# SiLPA_HE_LVDS_IFC.net
KiCad netlist of a schematic drawn in Altium Designer
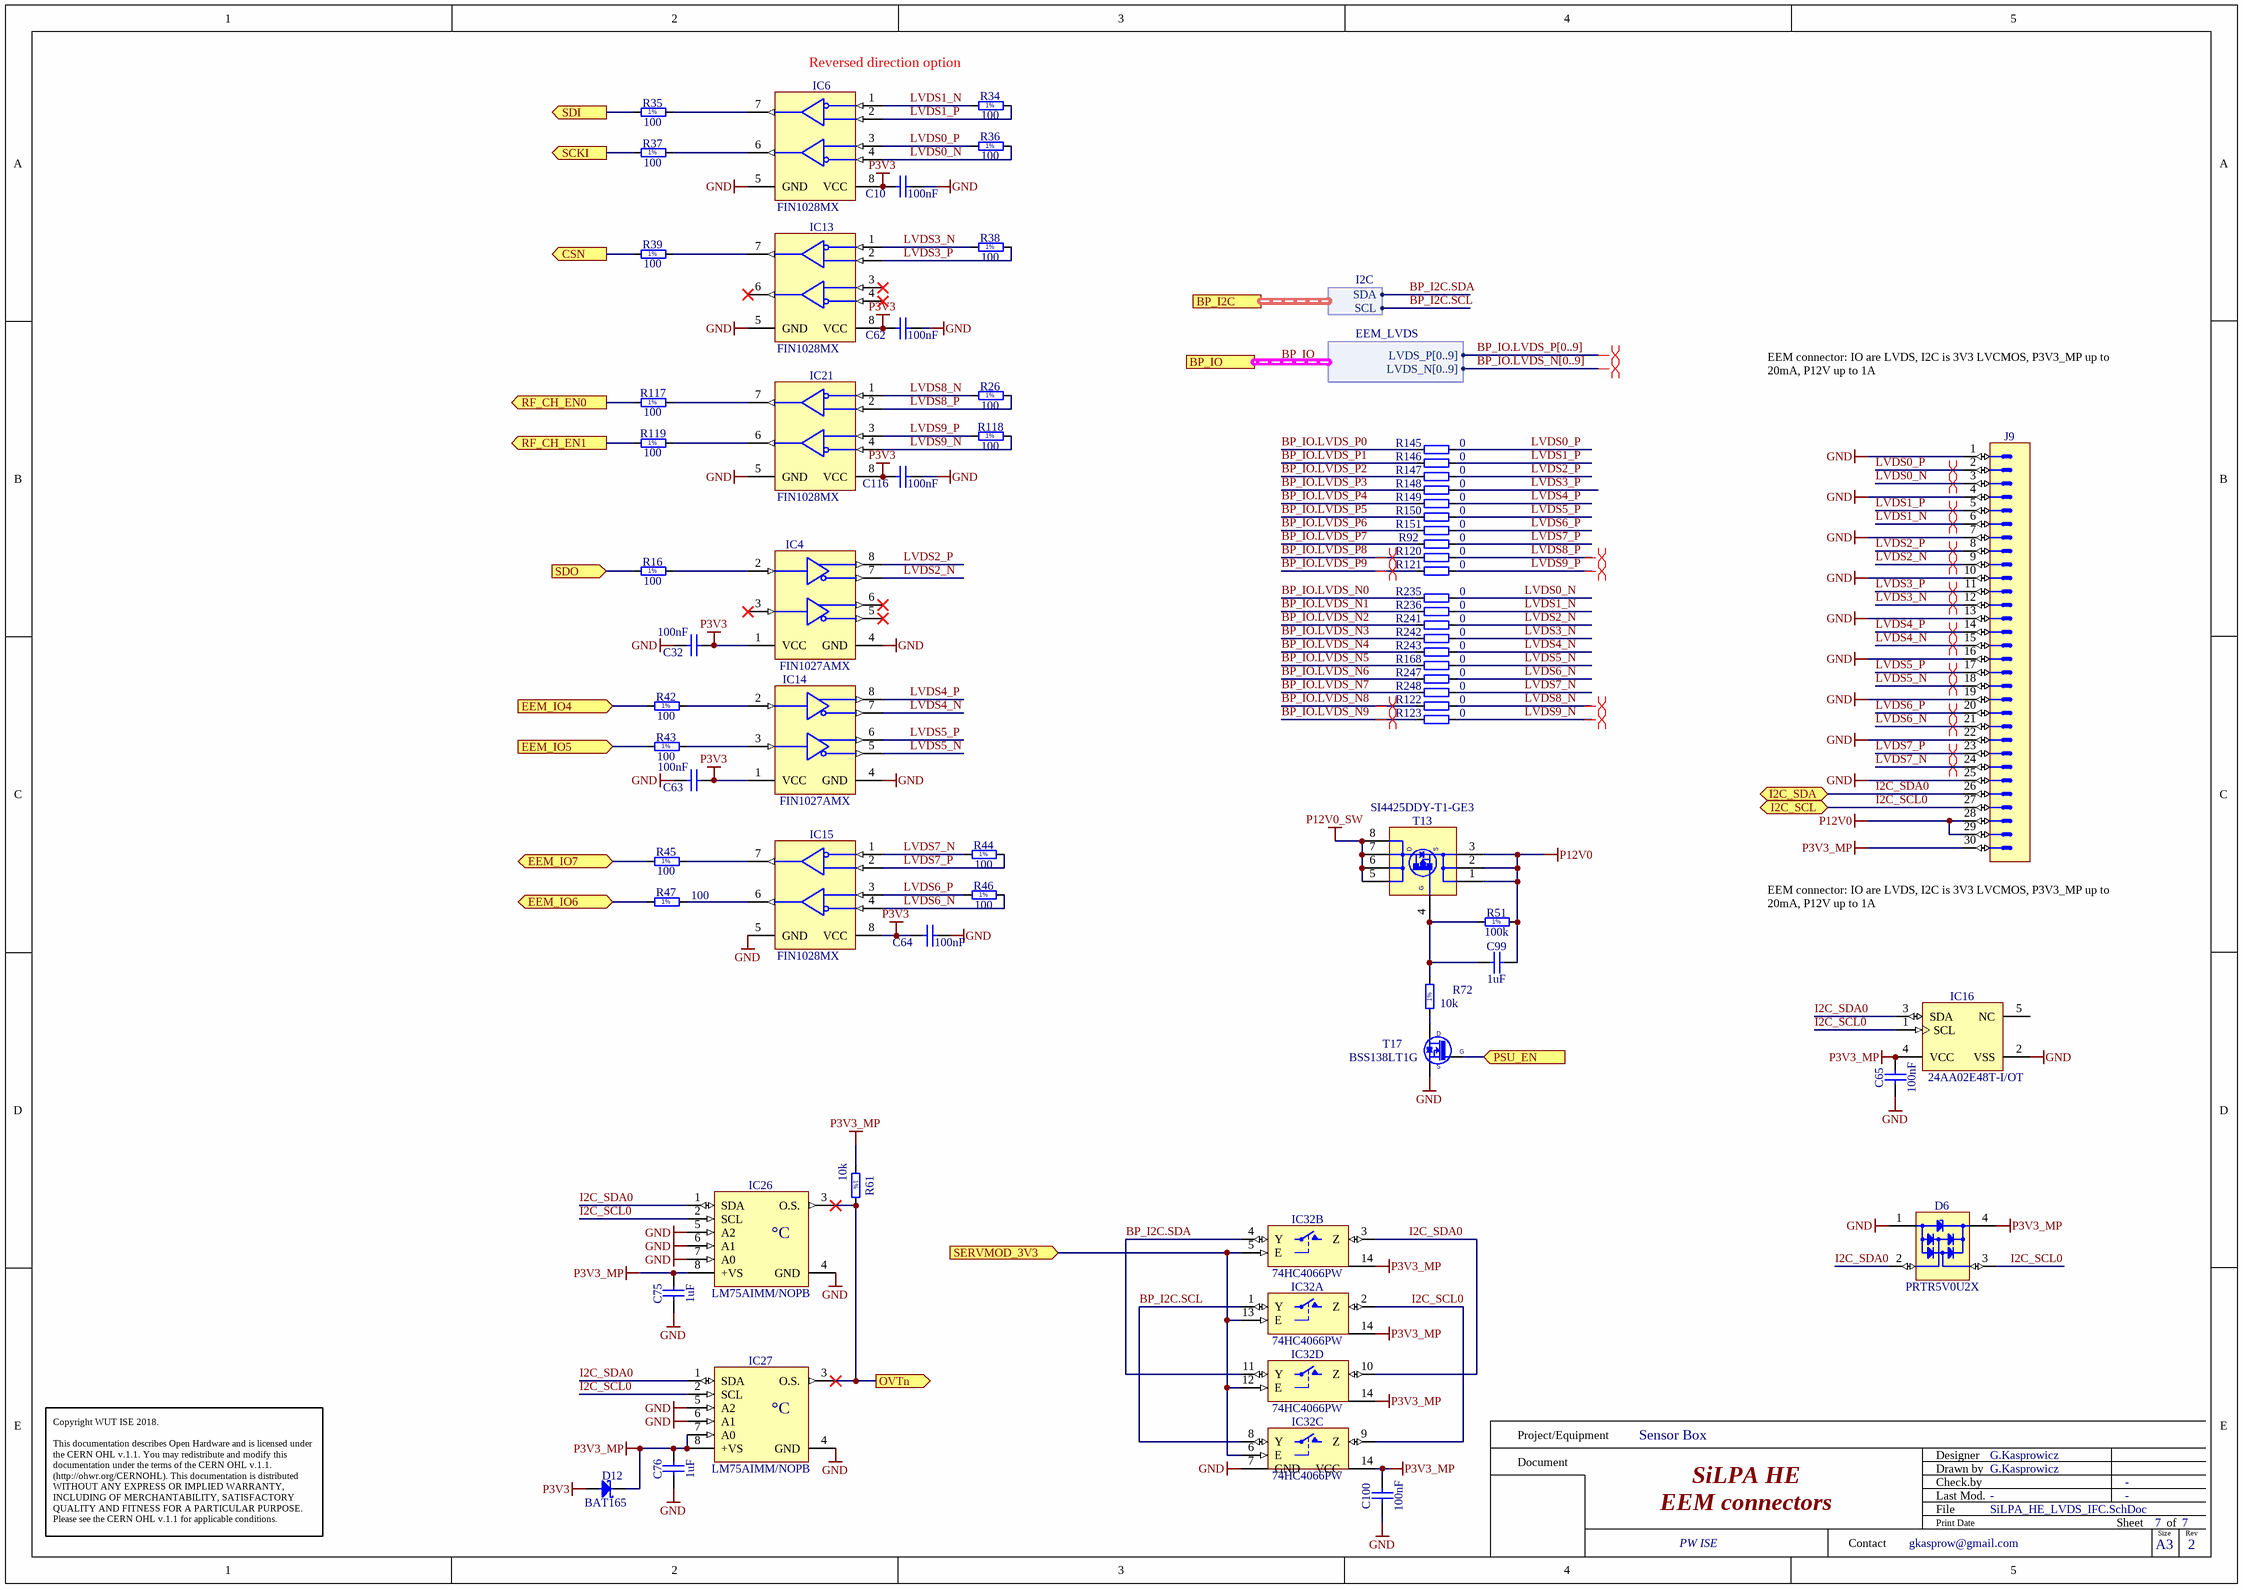
[diagram p0: SiLPA_HE_LVDS_IFC.SchDoc]

(export (version "E")
  (design (tool "Eeschema 10.0.6"))
  (components
    (comp (ref "C10")
      (value "100nF")
      (footprint "CAPC1005X55N")
      (description "Non-polarised capacitor")
      (fields
        (field (name "PART NUMBER") "CC0402_100NF_16V_10%_X5R")
        (field (name "VOLTAGE") "16V")
        (field (name "AUTHOR") "CERN DEM JLC")
      )
      (libsource (lib "Capacitors") (part "Capacitor - non polarized"))
    )
    (comp (ref "C32")
      (value "100nF")
      (footprint "CAPC1005X55N")
      (description "Non-polarised capacitor")
      (fields
        (field (name "PART NUMBER") "CC0402_100NF_16V_10%_X5R")
        (field (name "VOLTAGE") "16V")
        (field (name "AUTHOR") "CERN DEM JLC")
      )
      (libsource (lib "Capacitors") (part "Capacitor - non polarized"))
    )
    (comp (ref "C62")
      (value "100nF")
      (footprint "CAPC1005X55N")
      (description "Non-polarised capacitor")
      (fields
        (field (name "PART NUMBER") "CC0402_100NF_16V_10%_X5R")
        (field (name "VOLTAGE") "16V")
        (field (name "AUTHOR") "CERN DEM JLC")
      )
      (libsource (lib "Capacitors") (part "Capacitor - non polarized"))
    )
    (comp (ref "C63")
      (value "100nF")
      (footprint "CAPC1005X55N")
      (description "Non-polarised capacitor")
      (fields
        (field (name "PART NUMBER") "CC0402_100NF_16V_10%_X5R")
        (field (name "VOLTAGE") "16V")
        (field (name "AUTHOR") "CERN DEM JLC")
      )
      (libsource (lib "Capacitors") (part "Capacitor - non polarized"))
    )
    (comp (ref "C64")
      (value "100nF")
      (footprint "CAPC1005X55N")
      (description "Non-polarised capacitor")
      (fields
        (field (name "PART NUMBER") "CC0402_100NF_16V_10%_X5R")
        (field (name "VOLTAGE") "16V")
        (field (name "AUTHOR") "CERN DEM JLC")
      )
      (libsource (lib "Capacitors") (part "Capacitor - non polarized"))
    )
    (comp (ref "C65")
      (value "100nF")
      (footprint "CAPC1005X55N")
      (description "Non-polarised capacitor")
      (fields
        (field (name "PART NUMBER") "CC0402_100NF_16V_10%_X5R")
        (field (name "VOLTAGE") "16V")
        (field (name "AUTHOR") "CERN DEM JLC")
      )
      (libsource (lib "Capacitors") (part "Capacitor - non polarized"))
    )
    (comp (ref "C75")
      (value "1uF")
      (footprint "CAPC1005X55N")
      (description "Non-polarised capacitor")
      (fields
        (field (name "PART NUMBER") "CC0402_1UF_16V_10%_X5R")
        (field (name "VOLTAGE") "16V")
        (field (name "AUTHOR") "CERN DEM JLC")
      )
      (libsource (lib "Capacitors") (part "Capacitor - non polarized"))
    )
    (comp (ref "C76")
      (value "1uF")
      (footprint "CAPC1005X55N")
      (description "Non-polarised capacitor")
      (fields
        (field (name "PART NUMBER") "CC0402_1UF_16V_10%_X5R")
        (field (name "VOLTAGE") "16V")
        (field (name "AUTHOR") "CERN DEM JLC")
      )
      (libsource (lib "Capacitors") (part "Capacitor - non polarized"))
    )
    (comp (ref "C99")
      (value "1uF")
      (footprint "CAPC1005X55N")
      (description "Non-polarised capacitor")
      (fields
        (field (name "PART NUMBER") "CC0402_1UF_16V_10%_X5R")
        (field (name "VOLTAGE") "16V")
        (field (name "AUTHOR") "CERN DEM JLC")
      )
      (libsource (lib "Capacitors") (part "Capacitor - non polarized"))
    )
    (comp (ref "C100")
      (value "100nF")
      (footprint "CAPC1005X55N")
      (description "Non-polarised capacitor")
      (fields
        (field (name "PART NUMBER") "CC0402_100NF_16V_10%_X5R")
        (field (name "VOLTAGE") "16V")
        (field (name "AUTHOR") "CERN DEM JLC")
      )
      (libsource (lib "EEM_FMC_Carrier") (part "CC0402_100NF_16V_10%_X5R"))
    )
    (comp (ref "C116")
      (value "100nF")
      (footprint "CAPC1005X55N")
      (description "Non-polarised capacitor")
      (fields
        (field (name "PART NUMBER") "CC0402_100NF_16V_10%_X5R")
        (field (name "VOLTAGE") "16V")
        (field (name "AUTHOR") "CERN DEM JLC")
      )
      (libsource (lib "Capacitors") (part "Capacitor - non polarized"))
    )
    (comp (ref "D6")
      (value "PRTR5V0U2X")
      (footprint "SOT190P230X110-4N")
      (description "Ultra Low Capacitance Double Rail-to-Rail ESD Protection Diode")
      (fields
        (field (name "VOLTAGE") "5.5V")
        (field (name "MANUFACTURER") "NXP SEMICONDUCTORS")
        (field (name "AUTHOR") "CERN DEM JLC")
      )
      (libsource (lib "ICs And Semiconductors") (part "PRTR5V0U2X"))
    )
    (comp (ref "D12")
      (value "BAT165")
      (footprint "SOD2512X110N")
      (description "Schottky Diode")
      (fields
        (field (name "VOLTAGE") "40V")
        (field (name "POWER") "750mA")
        (field (name "AUTHOR") "CERN DEM JLC")
      )
      (libsource (lib "ICs And Semiconductors") (part "Diode Schottky"))
    )
    (comp (ref "IC4")
      (value "FIN1027AMX")
      (footprint "SOIC127P600X175-8N")
      (description "3.3V LVDS, 2-Bit, High-Speed, Differential Driver")
      (fields (field (name "MANUFACTURER") "ON Semiconductor") (field (name "AUTHOR") "GK"))
      (libsource (lib "LIBRARY_SCH") (part "IFC_FIN1027A"))
    )
    (comp (ref "IC6")
      (value "FIN1028MX")
      (footprint "SOIC127P600X175-8N")
      (description "3.3V LVDS 2-Bit High-Speed Differential Reciever")
      (fields (field (name "MANUFACTURER") "ON Semiconductor") (field (name "AUTHOR") "GK"))
      (libsource (lib "LIBRARY_SCH") (part "IFC_FIN1028"))
    )
    (comp (ref "IC13")
      (value "FIN1028MX")
      (footprint "SOIC127P600X175-8N")
      (description "3.3V LVDS 2-Bit High-Speed Differential Reciever")
      (fields (field (name "MANUFACTURER") "ON Semiconductor") (field (name "AUTHOR") "GK"))
      (libsource (lib "LIBRARY_SCH") (part "IFC_FIN1028"))
    )
    (comp (ref "IC14")
      (value "FIN1027AMX")
      (footprint "SOIC127P600X175-8N")
      (description "3.3V LVDS, 2-Bit, High-Speed, Differential Driver")
      (fields (field (name "MANUFACTURER") "ON Semiconductor") (field (name "AUTHOR") "GK"))
      (libsource (lib "LIBRARY_SCH") (part "IFC_FIN1027A"))
    )
    (comp (ref "IC15")
      (value "FIN1028MX")
      (footprint "SOIC127P600X175-8N")
      (description "3.3V LVDS 2-Bit High-Speed Differential Reciever")
      (fields (field (name "MANUFACTURER") "ON Semiconductor") (field (name "AUTHOR") "GK"))
      (libsource (lib "LIBRARY_SCH") (part "IFC_FIN1028"))
    )
    (comp (ref "IC16")
      (value "24AA02E48T-I/OT")
      (footprint "SOT95P280X145-5N")
      (description "1.7V-5.5V, 2K I2C Serial EEPROM With EUI-48 Node Identity")
      (fields (field (name "MANUFACTURER") "MICROCHIP TECHNOLOGY") (field (name "AUTHOR") "CERN DEM MR"))
      (libsource (lib "ICs And Semiconductors") (part "24AA02E48T-I/OT"))
    )
    (comp (ref "IC21")
      (value "FIN1028MX")
      (footprint "SOIC127P600X175-8N")
      (description "3.3V LVDS 2-Bit High-Speed Differential Reciever")
      (fields (field (name "MANUFACTURER") "ON Semiconductor") (field (name "AUTHOR") "GK"))
      (libsource (lib "LIBRARY_SCH") (part "IFC_FIN1028"))
    )
    (comp (ref "IC26")
      (value "LM75AIMM/NOPB")
      (footprint "SOP65P490X109-8N")
      (description "Digital Temperature Sensor and Thermal Watchdog with Two-Wire Interface")
      (fields (field (name "MANUFACTURER") "TEXAS INSTRUMENTS") (field (name "AUTHOR") "CERN DEM JLC"))
      (libsource (lib "ICs And Semiconductors") (part "LM75"))
    )
    (comp (ref "IC27")
      (value "LM75AIMM/NOPB")
      (footprint "SOP65P490X109-8N")
      (description "Digital Temperature Sensor and Thermal Watchdog with Two-Wire Interface")
      (fields (field (name "MANUFACTURER") "TEXAS INSTRUMENTS") (field (name "AUTHOR") "CERN DEM JLC"))
      (libsource (lib "ICs And Semiconductors") (part "LM75"))
    )
    (comp (ref "IC32")
      (value "74HC4066PW")
      (footprint "SOP65P640X110-14N")
      (fields (field (name "MANUFACTURER") "NXP SEMICONDUCTORS") (field (name "AUTHOR") "CERN DEM JLC"))
      (libsource (lib "EEM_FMC_Carrier") (part "74HC4066PW"))
    )
    (comp (ref "J9")
      (value "~")
      (footprint "3M_N2530-6002RB")
      (description "Connector 30 Male")
      (fields
        (field (name "PART NUMBER") "3M_N2530-6002RB")
        (field (name "MANUFACTURER") "3M")
        (field (name "AUTHOR") "CERN DEM JLC")
      )
      (libsource (lib "Connectors") (part "Connector 30 Male"))
    )
    (comp (ref "R16")
      (value "100")
      (footprint "RESC1005X40N")
      (description "Resistor - 1%")
      (fields
        (field (name "PART NUMBER") "R0402_100R_1%_0.0625W_100PPM")
        (field (name "POWER") "0.0625W")
        (field (name "AUTHOR") "CERN DEM JLC")
      )
      (libsource (lib "Resistors") (part "Resistor - 1%"))
    )
    (comp (ref "R26")
      (value "100")
      (footprint "RESC1005X40N")
      (description "Resistor - 1%")
      (fields
        (field (name "PART NUMBER") "R0402_100R_1%_0.0625W_100PPM")
        (field (name "POWER") "0.0625W")
        (field (name "AUTHOR") "CERN DEM JLC")
      )
      (libsource (lib "Resistors") (part "Resistor - 1%"))
    )
    (comp (ref "R34")
      (value "100")
      (footprint "RESC1005X40N")
      (description "Resistor - 1%")
      (fields
        (field (name "PART NUMBER") "R0402_100R_1%_0.0625W_100PPM")
        (field (name "POWER") "0.0625W")
        (field (name "AUTHOR") "CERN DEM JLC")
      )
      (libsource (lib "Resistors") (part "Resistor - 1%"))
    )
    (comp (ref "R35")
      (value "100")
      (footprint "RESC1005X40N")
      (description "Resistor - 1%")
      (fields
        (field (name "PART NUMBER") "R0402_100R_1%_0.0625W_100PPM")
        (field (name "POWER") "0.0625W")
        (field (name "AUTHOR") "CERN DEM JLC")
      )
      (libsource (lib "Resistors") (part "Resistor - 1%"))
    )
    (comp (ref "R36")
      (value "100")
      (footprint "RESC1005X40N")
      (description "Resistor - 1%")
      (fields
        (field (name "PART NUMBER") "R0402_100R_1%_0.0625W_100PPM")
        (field (name "POWER") "0.0625W")
        (field (name "AUTHOR") "CERN DEM JLC")
      )
      (libsource (lib "Resistors") (part "Resistor - 1%"))
    )
    (comp (ref "R37")
      (value "100")
      (footprint "RESC1005X40N")
      (description "Resistor - 1%")
      (fields
        (field (name "PART NUMBER") "R0402_100R_1%_0.0625W_100PPM")
        (field (name "POWER") "0.0625W")
        (field (name "AUTHOR") "CERN DEM JLC")
      )
      (libsource (lib "Resistors") (part "Resistor - 1%"))
    )
    (comp (ref "R38")
      (value "100")
      (footprint "RESC1005X40N")
      (description "Resistor - 1%")
      (fields
        (field (name "PART NUMBER") "R0402_100R_1%_0.0625W_100PPM")
        (field (name "POWER") "0.0625W")
        (field (name "AUTHOR") "CERN DEM JLC")
      )
      (libsource (lib "Resistors") (part "Resistor - 1%"))
    )
    (comp (ref "R39")
      (value "100")
      (footprint "RESC1005X40N")
      (description "Resistor - 1%")
      (fields
        (field (name "PART NUMBER") "R0402_100R_1%_0.0625W_100PPM")
        (field (name "POWER") "0.0625W")
        (field (name "AUTHOR") "CERN DEM JLC")
      )
      (libsource (lib "Resistors") (part "Resistor - 1%"))
    )
    (comp (ref "R42")
      (value "100")
      (footprint "RESC1005X40N")
      (description "Resistor - 1%")
      (fields
        (field (name "PART NUMBER") "R0402_100R_1%_0.0625W_100PPM")
        (field (name "POWER") "0.0625W")
        (field (name "AUTHOR") "CERN DEM JLC")
      )
      (libsource (lib "Resistors") (part "Resistor - 1%"))
    )
    (comp (ref "R43")
      (value "100")
      (footprint "RESC1005X40N")
      (description "Resistor - 1%")
      (fields
        (field (name "PART NUMBER") "R0402_100R_1%_0.0625W_100PPM")
        (field (name "POWER") "0.0625W")
        (field (name "AUTHOR") "CERN DEM JLC")
      )
      (libsource (lib "Resistors") (part "Resistor - 1%"))
    )
    (comp (ref "R44")
      (value "100")
      (footprint "RESC1005X40N")
      (description "Resistor - 1%")
      (fields
        (field (name "PART NUMBER") "R0402_100R_1%_0.0625W_100PPM")
        (field (name "POWER") "0.0625W")
        (field (name "AUTHOR") "CERN DEM JLC")
      )
      (libsource (lib "Resistors") (part "Resistor - 1%"))
    )
    (comp (ref "R45")
      (value "100")
      (footprint "RESC1005X40N")
      (description "Resistor - 1%")
      (fields
        (field (name "PART NUMBER") "R0402_100R_1%_0.0625W_100PPM")
        (field (name "POWER") "0.0625W")
        (field (name "AUTHOR") "CERN DEM JLC")
      )
      (libsource (lib "Resistors") (part "Resistor - 1%"))
    )
    (comp (ref "R46")
      (value "100")
      (footprint "RESC1005X40N")
      (description "Resistor - 1%")
      (fields
        (field (name "PART NUMBER") "R0402_100R_1%_0.0625W_100PPM")
        (field (name "POWER") "0.0625W")
        (field (name "AUTHOR") "CERN DEM JLC")
      )
      (libsource (lib "Resistors") (part "Resistor - 1%"))
    )
    (comp (ref "R47")
      (value "100")
      (footprint "RESC1005X40N")
      (description "Resistor - 1%")
      (fields
        (field (name "PART NUMBER") "R0402_100R_1%_0.0625W_100PPM")
        (field (name "POWER") "0.0625W")
        (field (name "AUTHOR") "CERN DEM JLC")
      )
      (libsource (lib "Resistors") (part "Resistor - 1%"))
    )
    (comp (ref "R51")
      (value "100k")
      (footprint "RESC1608X55N")
      (description "Resistor - 1%")
      (fields
        (field (name "PART NUMBER") "R0603_100K_1%_0.1W_100PPM")
        (field (name "POWER") "0.1W")
        (field (name "AUTHOR") "CERN DEM JLC")
      )
      (libsource (lib "Resistors") (part "Resistor - 1%"))
    )
    (comp (ref "R61")
      (value "10k")
      (footprint "RESC1005X40N")
      (description "Resistor - 1%")
      (fields
        (field (name "PART NUMBER") "R0402_10K_1%_0.0625W_100PPM")
        (field (name "POWER") "0.0625W")
        (field (name "AUTHOR") "CERN DEM JLC")
      )
      (libsource (lib "Resistors") (part "Resistor - 1%"))
    )
    (comp (ref "R72")
      (value "10k")
      (footprint "RESC1005X40N")
      (description "Resistor - 1%")
      (fields
        (field (name "PART NUMBER") "R0402_10K_1%_0.0625W_100PPM")
        (field (name "POWER") "0.0625W")
        (field (name "AUTHOR") "CERN DEM JLC")
      )
      (libsource (lib "Resistors") (part "Resistor - 1%"))
    )
    (comp (ref "R92")
      (value "0")
      (footprint "RESC1005X40N")
      (description "Resistor")
      (fields
        (field (name "PART NUMBER") "R0402_0R_JUMPER")
        (field (name "MANUFACTURER") "GENERIC")
        (field (name "AUTHOR") "CERN DEM JLC")
      )
      (libsource (lib "Resistors") (part "Resistor"))
    )
    (comp (ref "R117")
      (value "100")
      (footprint "RESC1005X40N")
      (description "Resistor - 1%")
      (fields
        (field (name "PART NUMBER") "R0402_100R_1%_0.0625W_100PPM")
        (field (name "POWER") "0.0625W")
        (field (name "AUTHOR") "CERN DEM JLC")
      )
      (libsource (lib "Resistors") (part "Resistor - 1%"))
    )
    (comp (ref "R118")
      (value "100")
      (footprint "RESC1005X40N")
      (description "Resistor - 1%")
      (fields
        (field (name "PART NUMBER") "R0402_100R_1%_0.0625W_100PPM")
        (field (name "POWER") "0.0625W")
        (field (name "AUTHOR") "CERN DEM JLC")
      )
      (libsource (lib "Resistors") (part "Resistor - 1%"))
    )
    (comp (ref "R119")
      (value "100")
      (footprint "RESC1005X40N")
      (description "Resistor - 1%")
      (fields
        (field (name "PART NUMBER") "R0402_100R_1%_0.0625W_100PPM")
        (field (name "POWER") "0.0625W")
        (field (name "AUTHOR") "CERN DEM JLC")
      )
      (libsource (lib "Resistors") (part "Resistor - 1%"))
    )
    (comp (ref "R120")
      (value "0")
      (footprint "RESC1005X40N")
      (description "Resistor")
      (fields
        (field (name "PART NUMBER") "R0402_0R_JUMPER")
        (field (name "MANUFACTURER") "GENERIC")
        (field (name "AUTHOR") "CERN DEM JLC")
      )
      (libsource (lib "Resistors") (part "Resistor"))
    )
    (comp (ref "R121")
      (value "0")
      (footprint "RESC1005X40N")
      (description "Resistor")
      (fields
        (field (name "PART NUMBER") "R0402_0R_JUMPER")
        (field (name "MANUFACTURER") "GENERIC")
        (field (name "AUTHOR") "CERN DEM JLC")
      )
      (libsource (lib "Resistors") (part "Resistor"))
    )
    (comp (ref "R122")
      (value "0")
      (footprint "RESC1005X40N")
      (description "Resistor")
      (fields
        (field (name "PART NUMBER") "R0402_0R_JUMPER")
        (field (name "MANUFACTURER") "GENERIC")
        (field (name "AUTHOR") "CERN DEM JLC")
      )
      (libsource (lib "Resistors") (part "Resistor"))
    )
    (comp (ref "R123")
      (value "0")
      (footprint "RESC1005X40N")
      (description "Resistor")
      (fields
        (field (name "PART NUMBER") "R0402_0R_JUMPER")
        (field (name "MANUFACTURER") "GENERIC")
        (field (name "AUTHOR") "CERN DEM JLC")
      )
      (libsource (lib "Resistors") (part "Resistor"))
    )
    (comp (ref "R145")
      (value "0")
      (footprint "RESC1005X40N")
      (description "Resistor")
      (fields
        (field (name "PART NUMBER") "R0402_0R_JUMPER")
        (field (name "MANUFACTURER") "GENERIC")
        (field (name "AUTHOR") "CERN DEM JLC")
      )
      (libsource (lib "Resistors") (part "Resistor"))
    )
    (comp (ref "R146")
      (value "0")
      (footprint "RESC1005X40N")
      (description "Resistor")
      (fields
        (field (name "PART NUMBER") "R0402_0R_JUMPER")
        (field (name "MANUFACTURER") "GENERIC")
        (field (name "AUTHOR") "CERN DEM JLC")
      )
      (libsource (lib "Resistors") (part "Resistor"))
    )
    (comp (ref "R147")
      (value "0")
      (footprint "RESC1005X40N")
      (description "Resistor")
      (fields
        (field (name "PART NUMBER") "R0402_0R_JUMPER")
        (field (name "MANUFACTURER") "GENERIC")
        (field (name "AUTHOR") "CERN DEM JLC")
      )
      (libsource (lib "Resistors") (part "Resistor"))
    )
    (comp (ref "R148")
      (value "0")
      (footprint "RESC1005X40N")
      (description "Resistor")
      (fields
        (field (name "PART NUMBER") "R0402_0R_JUMPER")
        (field (name "MANUFACTURER") "GENERIC")
        (field (name "AUTHOR") "CERN DEM JLC")
      )
      (libsource (lib "Resistors") (part "Resistor"))
    )
    (comp (ref "R149")
      (value "0")
      (footprint "RESC1005X40N")
      (description "Resistor")
      (fields
        (field (name "PART NUMBER") "R0402_0R_JUMPER")
        (field (name "MANUFACTURER") "GENERIC")
        (field (name "AUTHOR") "CERN DEM JLC")
      )
      (libsource (lib "Resistors") (part "Resistor"))
    )
    (comp (ref "R150")
      (value "0")
      (footprint "RESC1005X40N")
      (description "Resistor")
      (fields
        (field (name "PART NUMBER") "R0402_0R_JUMPER")
        (field (name "MANUFACTURER") "GENERIC")
        (field (name "AUTHOR") "CERN DEM JLC")
      )
      (libsource (lib "Resistors") (part "Resistor"))
    )
    (comp (ref "R151")
      (value "0")
      (footprint "RESC1005X40N")
      (description "Resistor")
      (fields
        (field (name "PART NUMBER") "R0402_0R_JUMPER")
        (field (name "MANUFACTURER") "GENERIC")
        (field (name "AUTHOR") "CERN DEM JLC")
      )
      (libsource (lib "Resistors") (part "Resistor"))
    )
    (comp (ref "R168")
      (value "0")
      (footprint "RESC1005X40N")
      (description "Resistor")
      (fields
        (field (name "PART NUMBER") "R0402_0R_JUMPER")
        (field (name "MANUFACTURER") "GENERIC")
        (field (name "AUTHOR") "CERN DEM JLC")
      )
      (libsource (lib "Resistors") (part "Resistor"))
    )
    (comp (ref "R235")
      (value "0")
      (footprint "RESC1005X40N")
      (description "Resistor")
      (fields
        (field (name "PART NUMBER") "R0402_0R_JUMPER")
        (field (name "MANUFACTURER") "GENERIC")
        (field (name "AUTHOR") "CERN DEM JLC")
      )
      (libsource (lib "Resistors") (part "Resistor"))
    )
    (comp (ref "R236")
      (value "0")
      (footprint "RESC1005X40N")
      (description "Resistor")
      (fields
        (field (name "PART NUMBER") "R0402_0R_JUMPER")
        (field (name "MANUFACTURER") "GENERIC")
        (field (name "AUTHOR") "CERN DEM JLC")
      )
      (libsource (lib "Resistors") (part "Resistor"))
    )
    (comp (ref "R241")
      (value "0")
      (footprint "RESC1005X40N")
      (description "Resistor")
      (fields
        (field (name "PART NUMBER") "R0402_0R_JUMPER")
        (field (name "MANUFACTURER") "GENERIC")
        (field (name "AUTHOR") "CERN DEM JLC")
      )
      (libsource (lib "Resistors") (part "Resistor"))
    )
    (comp (ref "R242")
      (value "0")
      (footprint "RESC1005X40N")
      (description "Resistor")
      (fields
        (field (name "PART NUMBER") "R0402_0R_JUMPER")
        (field (name "MANUFACTURER") "GENERIC")
        (field (name "AUTHOR") "CERN DEM JLC")
      )
      (libsource (lib "Resistors") (part "Resistor"))
    )
    (comp (ref "R243")
      (value "0")
      (footprint "RESC1005X40N")
      (description "Resistor")
      (fields
        (field (name "PART NUMBER") "R0402_0R_JUMPER")
        (field (name "MANUFACTURER") "GENERIC")
        (field (name "AUTHOR") "CERN DEM JLC")
      )
      (libsource (lib "Resistors") (part "Resistor"))
    )
    (comp (ref "R247")
      (value "0")
      (footprint "RESC1005X40N")
      (description "Resistor")
      (fields
        (field (name "PART NUMBER") "R0402_0R_JUMPER")
        (field (name "MANUFACTURER") "GENERIC")
        (field (name "AUTHOR") "CERN DEM JLC")
      )
      (libsource (lib "Resistors") (part "Resistor"))
    )
    (comp (ref "R248")
      (value "0")
      (footprint "RESC1005X40N")
      (description "Resistor")
      (fields
        (field (name "PART NUMBER") "R0402_0R_JUMPER")
        (field (name "MANUFACTURER") "GENERIC")
        (field (name "AUTHOR") "CERN DEM JLC")
      )
      (libsource (lib "Resistors") (part "Resistor"))
    )
    (comp (ref "T13")
      (value "SI4425DDY-T1-GE3")
      (footprint "SOIC127P600X175-8N")
      (description "-30V -19.7A P-Channel MOSFET")
      (fields (field (name "MANUFACTURER") "VISHAY SILICONIX") (field (name "AUTHOR") "CERN DEM MR"))
      (libsource (lib "ICs And Semiconductors") (part "SI4425DDY"))
    )
    (comp (ref "T17")
      (value "BSS138LT1G")
      (footprint "SOT95P240X110-3N")
      (description "N-CHANNEL MOSFET WITH DIODE")
      (fields (field (name "MANUFACTURER") "ON SEMICONDUCTOR") (field (name "AUTHOR") "CERN DEM JLC"))
      (libsource (lib "ICs And Semiconductors") (part "N-MOSFET-D 1G 2S 3D"))
    )
  )
  (nets
    (net (code "3") (name "/BP_I2C.SCL") (class "Default")
      (node (ref "IC32") (pin "1") (pinfunction "Y_1") (pintype "bidirectional"))
      (node (ref "IC32") (pin "8") (pinfunction "Y_8") (pintype "bidirectional"))
    )
    (net (code "4") (name "/BP_I2C.SDA") (class "Default")
      (node (ref "IC32") (pin "11") (pinfunction "Y_11") (pintype "bidirectional"))
      (node (ref "IC32") (pin "4") (pinfunction "Y_4") (pintype "bidirectional"))
    )
    (net (code "5") (name "/BP_IO.LVDS_N0") (class "Default")
      (node (ref "R235") (pin "1") (pinfunction "1_1") (pintype "passive"))
    )
    (net (code "6") (name "/BP_IO.LVDS_N1") (class "Default")
      (node (ref "R236") (pin "1") (pinfunction "1_1") (pintype "passive"))
    )
    (net (code "7") (name "/BP_IO.LVDS_N2") (class "Default")
      (node (ref "R241") (pin "1") (pinfunction "1_1") (pintype "passive"))
    )
    (net (code "8") (name "/BP_IO.LVDS_N3") (class "Default")
      (node (ref "R242") (pin "1") (pinfunction "1_1") (pintype "passive"))
    )
    (net (code "9") (name "/BP_IO.LVDS_N4") (class "Default")
      (node (ref "R243") (pin "1") (pinfunction "1_1") (pintype "passive"))
    )
    (net (code "10") (name "/BP_IO.LVDS_N5") (class "Default")
      (node (ref "R168") (pin "1") (pinfunction "1_1") (pintype "passive"))
    )
    (net (code "11") (name "/BP_IO.LVDS_N6") (class "Default")
      (node (ref "R247") (pin "1") (pinfunction "1_1") (pintype "passive"))
    )
    (net (code "12") (name "/BP_IO.LVDS_N7") (class "Default")
      (node (ref "R248") (pin "1") (pinfunction "1_1") (pintype "passive"))
    )
    (net (code "13") (name "/BP_IO.LVDS_N8") (class "Default")
      (node (ref "R122") (pin "1") (pinfunction "1_1") (pintype "passive"))
    )
    (net (code "14") (name "/BP_IO.LVDS_N9") (class "Default")
      (node (ref "R123") (pin "1") (pinfunction "1_1") (pintype "passive"))
    )
    (net (code "16") (name "/BP_IO.LVDS_P0") (class "Default")
      (node (ref "R145") (pin "1") (pinfunction "1_1") (pintype "passive"))
    )
    (net (code "17") (name "/BP_IO.LVDS_P1") (class "Default")
      (node (ref "R146") (pin "1") (pinfunction "1_1") (pintype "passive"))
    )
    (net (code "18") (name "/BP_IO.LVDS_P2") (class "Default")
      (node (ref "R147") (pin "1") (pinfunction "1_1") (pintype "passive"))
    )
    (net (code "19") (name "/BP_IO.LVDS_P3") (class "Default")
      (node (ref "R148") (pin "1") (pinfunction "1_1") (pintype "passive"))
    )
    (net (code "20") (name "/BP_IO.LVDS_P4") (class "Default")
      (node (ref "R149") (pin "1") (pinfunction "1_1") (pintype "passive"))
    )
    (net (code "21") (name "/BP_IO.LVDS_P5") (class "Default")
      (node (ref "R150") (pin "1") (pinfunction "1_1") (pintype "passive"))
    )
    (net (code "22") (name "/BP_IO.LVDS_P6") (class "Default")
      (node (ref "R151") (pin "1") (pinfunction "1_1") (pintype "passive"))
    )
    (net (code "23") (name "/BP_IO.LVDS_P7") (class "Default")
      (node (ref "R92") (pin "1") (pinfunction "1_1") (pintype "passive"))
    )
    (net (code "24") (name "/BP_IO.LVDS_P8") (class "Default")
      (node (ref "R120") (pin "1") (pinfunction "1_1") (pintype "passive"))
    )
    (net (code "25") (name "/BP_IO.LVDS_P9") (class "Default")
      (node (ref "R121") (pin "1") (pinfunction "1_1") (pintype "passive"))
    )
    (net (code "28") (name "/CSN") (class "Default")
      (node (ref "R39") (pin "1") (pinfunction "1_1") (pintype "passive"))
    )
    (net (code "29") (name "/EEM_IO4") (class "Default")
      (node (ref "R42") (pin "1") (pinfunction "1_1") (pintype "passive"))
    )
    (net (code "30") (name "/EEM_IO5") (class "Default")
      (node (ref "R43") (pin "1") (pinfunction "1_1") (pintype "passive"))
    )
    (net (code "31") (name "/EEM_IO6") (class "Default")
      (node (ref "R47") (pin "1") (pinfunction "1_1") (pintype "passive"))
    )
    (net (code "32") (name "/EEM_IO7") (class "Default")
      (node (ref "R45") (pin "1") (pinfunction "1_1") (pintype "passive"))
    )
    (net (code "33") (name "/I2C_SCL0") (class "Default")
      (node (ref "D6") (pin "3") (pinfunction "I/O2_3") (pintype "bidirectional"))
      (node (ref "IC16") (pin "1") (pinfunction "SCL_1") (pintype "input"))
      (node (ref "IC26") (pin "2") (pinfunction "SCL_2") (pintype "input"))
      (node (ref "IC27") (pin "2") (pinfunction "SCL_2") (pintype "input"))
      (node (ref "IC32") (pin "2") (pinfunction "Z_2") (pintype "bidirectional"))
      (node (ref "IC32") (pin "9") (pinfunction "Z_9") (pintype "bidirectional"))
      (node (ref "J9") (pin "27") (pinfunction "27_27") (pintype "bidirectional"))
    )
    (net (code "34") (name "/I2C_SDA0") (class "Default")
      (node (ref "D6") (pin "2") (pinfunction "I/O1_2") (pintype "bidirectional"))
      (node (ref "IC16") (pin "3") (pinfunction "SDA_3") (pintype "bidirectional"))
      (node (ref "IC26") (pin "1") (pinfunction "SDA_1") (pintype "bidirectional"))
      (node (ref "IC27") (pin "1") (pinfunction "SDA_1") (pintype "bidirectional"))
      (node (ref "IC32") (pin "10") (pinfunction "Z_10") (pintype "bidirectional"))
      (node (ref "IC32") (pin "3") (pinfunction "Z_3") (pintype "bidirectional"))
      (node (ref "J9") (pin "26") (pinfunction "26_26") (pintype "bidirectional"))
    )
    (net (code "35") (name "/LVDS0_N") (class "Default")
      (node (ref "IC6") (pin "4") (pinfunction "RIN2-_4") (pintype "input"))
      (node (ref "J9") (pin "3") (pinfunction "3_3") (pintype "bidirectional"))
      (node (ref "R235") (pin "2") (pinfunction "2_2") (pintype "passive"))
      (node (ref "R36") (pin "2") (pinfunction "2_2") (pintype "passive"))
    )
    (net (code "36") (name "/LVDS0_P") (class "Default")
      (node (ref "IC6") (pin "3") (pinfunction "RIN2+_3") (pintype "input"))
      (node (ref "J9") (pin "2") (pinfunction "2_2") (pintype "bidirectional"))
      (node (ref "R145") (pin "2") (pinfunction "2_2") (pintype "passive"))
      (node (ref "R36") (pin "1") (pinfunction "1_1") (pintype "passive"))
    )
    (net (code "37") (name "/LVDS1_N") (class "Default")
      (node (ref "IC6") (pin "1") (pinfunction "RIN1-_1") (pintype "input"))
      (node (ref "J9") (pin "6") (pinfunction "6_6") (pintype "bidirectional"))
      (node (ref "R236") (pin "2") (pinfunction "2_2") (pintype "passive"))
      (node (ref "R34") (pin "1") (pinfunction "1_1") (pintype "passive"))
    )
    (net (code "38") (name "/LVDS1_P") (class "Default")
      (node (ref "IC6") (pin "2") (pinfunction "RIN1+_2") (pintype "input"))
      (node (ref "J9") (pin "5") (pinfunction "5_5") (pintype "bidirectional"))
      (node (ref "R146") (pin "2") (pinfunction "2_2") (pintype "passive"))
      (node (ref "R34") (pin "2") (pinfunction "2_2") (pintype "passive"))
    )
    (net (code "39") (name "/LVDS2_N") (class "Default")
      (node (ref "IC4") (pin "7") (pinfunction "DOUT-_7") (pintype "output"))
      (node (ref "J9") (pin "9") (pinfunction "9_9") (pintype "bidirectional"))
      (node (ref "R241") (pin "2") (pinfunction "2_2") (pintype "passive"))
    )
    (net (code "40") (name "/LVDS2_P") (class "Default")
      (node (ref "IC4") (pin "8") (pinfunction "DOUT+_8") (pintype "output"))
      (node (ref "J9") (pin "8") (pinfunction "8_8") (pintype "bidirectional"))
      (node (ref "R147") (pin "2") (pinfunction "2_2") (pintype "passive"))
    )
    (net (code "41") (name "/LVDS3_N") (class "Default")
      (node (ref "IC13") (pin "1") (pinfunction "RIN1-_1") (pintype "input"))
      (node (ref "J9") (pin "12") (pinfunction "12_12") (pintype "bidirectional"))
      (node (ref "R242") (pin "2") (pinfunction "2_2") (pintype "passive"))
      (node (ref "R38") (pin "1") (pinfunction "1_1") (pintype "passive"))
    )
    (net (code "42") (name "/LVDS3_P") (class "Default")
      (node (ref "IC13") (pin "2") (pinfunction "RIN1+_2") (pintype "input"))
      (node (ref "J9") (pin "11") (pinfunction "11_11") (pintype "bidirectional"))
      (node (ref "R148") (pin "2") (pinfunction "2_2") (pintype "passive"))
      (node (ref "R38") (pin "2") (pinfunction "2_2") (pintype "passive"))
    )
    (net (code "43") (name "/LVDS4_N") (class "Default")
      (node (ref "IC14") (pin "7") (pinfunction "DOUT-_7") (pintype "output"))
      (node (ref "J9") (pin "15") (pinfunction "15_15") (pintype "bidirectional"))
      (node (ref "R243") (pin "2") (pinfunction "2_2") (pintype "passive"))
    )
    (net (code "44") (name "/LVDS4_P") (class "Default")
      (node (ref "IC14") (pin "8") (pinfunction "DOUT+_8") (pintype "output"))
      (node (ref "J9") (pin "14") (pinfunction "14_14") (pintype "bidirectional"))
      (node (ref "R149") (pin "2") (pinfunction "2_2") (pintype "passive"))
    )
    (net (code "45") (name "/LVDS5_N") (class "Default")
      (node (ref "IC14") (pin "5") (pinfunction "DOUT-_5") (pintype "output"))
      (node (ref "J9") (pin "18") (pinfunction "18_18") (pintype "bidirectional"))
      (node (ref "R168") (pin "2") (pinfunction "2_2") (pintype "passive"))
    )
    (net (code "46") (name "/LVDS5_P") (class "Default")
      (node (ref "IC14") (pin "6") (pinfunction "DOUT+_6") (pintype "output"))
      (node (ref "J9") (pin "17") (pinfunction "17_17") (pintype "bidirectional"))
      (node (ref "R150") (pin "2") (pinfunction "2_2") (pintype "passive"))
    )
    (net (code "47") (name "/LVDS6_N") (class "Default")
      (node (ref "IC15") (pin "4") (pinfunction "RIN2-_4") (pintype "input"))
      (node (ref "J9") (pin "21") (pinfunction "21_21") (pintype "bidirectional"))
      (node (ref "R247") (pin "2") (pinfunction "2_2") (pintype "passive"))
      (node (ref "R46") (pin "2") (pinfunction "2_2") (pintype "passive"))
    )
    (net (code "48") (name "/LVDS6_P") (class "Default")
      (node (ref "IC15") (pin "3") (pinfunction "RIN2+_3") (pintype "input"))
      (node (ref "J9") (pin "20") (pinfunction "20_20") (pintype "bidirectional"))
      (node (ref "R151") (pin "2") (pinfunction "2_2") (pintype "passive"))
      (node (ref "R46") (pin "1") (pinfunction "1_1") (pintype "passive"))
    )
    (net (code "49") (name "/LVDS7_N") (class "Default")
      (node (ref "IC15") (pin "1") (pinfunction "RIN1-_1") (pintype "input"))
      (node (ref "J9") (pin "24") (pinfunction "24_24") (pintype "bidirectional"))
      (node (ref "R248") (pin "2") (pinfunction "2_2") (pintype "passive"))
      (node (ref "R44") (pin "1") (pinfunction "1_1") (pintype "passive"))
    )
    (net (code "50") (name "/LVDS7_P") (class "Default")
      (node (ref "IC15") (pin "2") (pinfunction "RIN1+_2") (pintype "input"))
      (node (ref "J9") (pin "23") (pinfunction "23_23") (pintype "bidirectional"))
      (node (ref "R44") (pin "2") (pinfunction "2_2") (pintype "passive"))
      (node (ref "R92") (pin "2") (pinfunction "2_2") (pintype "passive"))
    )
    (net (code "51") (name "/LVDS8_N") (class "Default")
      (node (ref "IC21") (pin "1") (pinfunction "RIN1-_1") (pintype "input"))
      (node (ref "R122") (pin "2") (pinfunction "2_2") (pintype "passive"))
      (node (ref "R26") (pin "1") (pinfunction "1_1") (pintype "passive"))
    )
    (net (code "52") (name "/LVDS8_P") (class "Default")
      (node (ref "IC21") (pin "2") (pinfunction "RIN1+_2") (pintype "input"))
      (node (ref "R120") (pin "2") (pinfunction "2_2") (pintype "passive"))
      (node (ref "R26") (pin "2") (pinfunction "2_2") (pintype "passive"))
    )
    (net (code "53") (name "/LVDS9_N") (class "Default")
      (node (ref "IC21") (pin "4") (pinfunction "RIN2-_4") (pintype "input"))
      (node (ref "R118") (pin "2") (pinfunction "2_2") (pintype "passive"))
      (node (ref "R123") (pin "2") (pinfunction "2_2") (pintype "passive"))
    )
    (net (code "54") (name "/LVDS9_P") (class "Default")
      (node (ref "IC21") (pin "3") (pinfunction "RIN2+_3") (pintype "input"))
      (node (ref "R118") (pin "1") (pinfunction "1_1") (pintype "passive"))
      (node (ref "R121") (pin "2") (pinfunction "2_2") (pintype "passive"))
    )
    (net (code "55") (name "/OVTn") (class "Default")
      (node (ref "IC26") (pin "3") (pinfunction "O.S._3") (pintype "output"))
      (node (ref "IC27") (pin "3") (pinfunction "O.S._3") (pintype "output"))
      (node (ref "R61") (pin "2") (pinfunction "2_2") (pintype "passive"))
    )
    (net (code "56") (name "/PSU_EN") (class "Default")
      (node (ref "T17") (pin "1") (pinfunction "G_1") (pintype "passive"))
    )
    (net (code "57") (name "/RF_CH_EN0") (class "Default")
      (node (ref "R117") (pin "1") (pinfunction "1_1") (pintype "passive"))
    )
    (net (code "58") (name "/RF_CH_EN1") (class "Default")
      (node (ref "R119") (pin "1") (pinfunction "1_1") (pintype "passive"))
    )
    (net (code "59") (name "/SCKI") (class "Default")
      (node (ref "R37") (pin "1") (pinfunction "1_1") (pintype "passive"))
    )
    (net (code "60") (name "/SDI") (class "Default")
      (node (ref "R35") (pin "1") (pinfunction "1_1") (pintype "passive"))
    )
    (net (code "61") (name "/SDO") (class "Default")
      (node (ref "R16") (pin "1") (pinfunction "1_1") (pintype "passive"))
    )
    (net (code "62") (name "/SERVMOD_3V3") (class "Default")
      (node (ref "IC32") (pin "12") (pinfunction "E_12") (pintype "input"))
      (node (ref "IC32") (pin "13") (pinfunction "E_13") (pintype "input"))
      (node (ref "IC32") (pin "5") (pinfunction "E_5") (pintype "input"))
      (node (ref "IC32") (pin "6") (pinfunction "E_6") (pintype "input"))
    )
    (net (code "64") (name "GND") (class "Default")
      (node (ref "C10") (pin "1") (pinfunction "1_1") (pintype "passive"))
      (node (ref "C100") (pin "1") (pinfunction "1_1") (pintype "passive"))
      (node (ref "C116") (pin "1") (pinfunction "1_1") (pintype "passive"))
      (node (ref "C32") (pin "1") (pinfunction "1_1") (pintype "passive"))
      (node (ref "C62") (pin "1") (pinfunction "1_1") (pintype "passive"))
      (node (ref "C63") (pin "1") (pinfunction "1_1") (pintype "passive"))
      (node (ref "C64") (pin "1") (pinfunction "1_1") (pintype "passive"))
      (node (ref "C65") (pin "1") (pinfunction "1_1") (pintype "passive"))
      (node (ref "C75") (pin "1") (pinfunction "1_1") (pintype "passive"))
      (node (ref "C76") (pin "1") (pinfunction "1_1") (pintype "passive"))
      (node (ref "D6") (pin "1") (pinfunction "GND_1") (pintype "power_in"))
      (node (ref "IC13") (pin "5") (pinfunction "GND_5") (pintype "power_in"))
      (node (ref "IC14") (pin "4") (pinfunction "GND_4") (pintype "power_in"))
      (node (ref "IC15") (pin "5") (pinfunction "GND_5") (pintype "power_in"))
      (node (ref "IC16") (pin "2") (pinfunction "VSS_2") (pintype "power_in"))
      (node (ref "IC21") (pin "5") (pinfunction "GND_5") (pintype "power_in"))
      (node (ref "IC26") (pin "4") (pinfunction "GND_4") (pintype "power_in"))
      (node (ref "IC26") (pin "5") (pinfunction "A2_5") (pintype "input"))
      (node (ref "IC26") (pin "6") (pinfunction "A1_6") (pintype "input"))
      (node (ref "IC26") (pin "7") (pinfunction "A0_7") (pintype "input"))
      (node (ref "IC27") (pin "4") (pinfunction "GND_4") (pintype "power_in"))
      (node (ref "IC27") (pin "5") (pinfunction "A2_5") (pintype "input"))
      (node (ref "IC27") (pin "6") (pinfunction "A1_6") (pintype "input"))
      (node (ref "IC32") (pin "7") (pinfunction "GND_7") (pintype "power_in"))
      (node (ref "IC4") (pin "4") (pinfunction "GND_4") (pintype "power_in"))
      (node (ref "IC6") (pin "5") (pinfunction "GND_5") (pintype "power_in"))
      (node (ref "J9") (pin "1") (pinfunction "1_1") (pintype "bidirectional"))
      (node (ref "J9") (pin "10") (pinfunction "10_10") (pintype "bidirectional"))
      (node (ref "J9") (pin "13") (pinfunction "13_13") (pintype "bidirectional"))
      (node (ref "J9") (pin "16") (pinfunction "16_16") (pintype "bidirectional"))
      (node (ref "J9") (pin "19") (pinfunction "19_19") (pintype "bidirectional"))
      (node (ref "J9") (pin "22") (pinfunction "22_22") (pintype "bidirectional"))
      (node (ref "J9") (pin "25") (pinfunction "25_25") (pintype "bidirectional"))
      (node (ref "J9") (pin "4") (pinfunction "4_4") (pintype "bidirectional"))
      (node (ref "J9") (pin "7") (pinfunction "7_7") (pintype "bidirectional"))
      (node (ref "T17") (pin "2") (pinfunction "S_2") (pintype "passive"))
    )
    (net (code "65") (name "Net-(C99-Pad1)") (class "Default")
      (node (ref "C99") (pin "1") (pinfunction "1_1") (pintype "passive"))
      (node (ref "R51") (pin "1") (pinfunction "1_1") (pintype "passive"))
      (node (ref "R72") (pin "2") (pinfunction "2_2") (pintype "passive"))
      (node (ref "T13") (pin "4") (pinfunction "S_4") (pintype "passive"))
    )
    (net (code "66") (name "Net-(IC4-DIN1)") (class "Default")
      (node (ref "IC4") (pin "2") (pinfunction "DIN1_2") (pintype "input"))
      (node (ref "R16") (pin "2") (pinfunction "2_2") (pintype "passive"))
    )
    (net (code "67") (name "Net-(IC6-ROUT1)") (class "Default")
      (node (ref "IC6") (pin "7") (pinfunction "ROUT1_7") (pintype "output"))
      (node (ref "R35") (pin "2") (pinfunction "2_2") (pintype "passive"))
    )
    (net (code "68") (name "Net-(IC6-ROUT2)") (class "Default")
      (node (ref "IC6") (pin "6") (pinfunction "ROUT2_6") (pintype "output"))
      (node (ref "R37") (pin "2") (pinfunction "2_2") (pintype "passive"))
    )
    (net (code "69") (name "Net-(IC13-ROUT1)") (class "Default")
      (node (ref "IC13") (pin "7") (pinfunction "ROUT1_7") (pintype "output"))
      (node (ref "R39") (pin "2") (pinfunction "2_2") (pintype "passive"))
    )
    (net (code "70") (name "Net-(IC14-DIN1)") (class "Default")
      (node (ref "IC14") (pin "2") (pinfunction "DIN1_2") (pintype "input"))
      (node (ref "R42") (pin "2") (pinfunction "2_2") (pintype "passive"))
    )
    (net (code "71") (name "Net-(IC14-DIN2RIN-)") (class "Default")
      (node (ref "IC14") (pin "3") (pinfunction "DIN2RIN-_3") (pintype "input"))
      (node (ref "R43") (pin "2") (pinfunction "2_2") (pintype "passive"))
    )
    (net (code "72") (name "Net-(IC15-ROUT1)") (class "Default")
      (node (ref "IC15") (pin "7") (pinfunction "ROUT1_7") (pintype "output"))
      (node (ref "R45") (pin "2") (pinfunction "2_2") (pintype "passive"))
    )
    (net (code "73") (name "Net-(IC15-ROUT2)") (class "Default")
      (node (ref "IC15") (pin "6") (pinfunction "ROUT2_6") (pintype "output"))
      (node (ref "R47") (pin "2") (pinfunction "2_2") (pintype "passive"))
    )
    (net (code "74") (name "Net-(IC21-ROUT1)") (class "Default")
      (node (ref "IC21") (pin "7") (pinfunction "ROUT1_7") (pintype "output"))
      (node (ref "R117") (pin "2") (pinfunction "2_2") (pintype "passive"))
    )
    (net (code "75") (name "Net-(IC21-ROUT2)") (class "Default")
      (node (ref "IC21") (pin "6") (pinfunction "ROUT2_6") (pintype "output"))
      (node (ref "R119") (pin "2") (pinfunction "2_2") (pintype "passive"))
    )
    (net (code "76") (name "Net-(T17-D)") (class "Default")
      (node (ref "R72") (pin "1") (pinfunction "1_1") (pintype "passive"))
      (node (ref "T17") (pin "3") (pinfunction "D_3") (pintype "passive"))
    )
    (net (code "77") (name "P3V3") (class "Default")
      (node (ref "C10") (pin "2") (pinfunction "2_2") (pintype "passive"))
      (node (ref "C116") (pin "2") (pinfunction "2_2") (pintype "passive"))
      (node (ref "C32") (pin "2") (pinfunction "2_2") (pintype "passive"))
      (node (ref "C62") (pin "2") (pinfunction "2_2") (pintype "passive"))
      (node (ref "C63") (pin "2") (pinfunction "2_2") (pintype "passive"))
      (node (ref "C64") (pin "2") (pinfunction "2_2") (pintype "passive"))
      (node (ref "D12") (pin "2") (pinfunction "A_2") (pintype "passive"))
      (node (ref "IC13") (pin "8") (pinfunction "VCC_8") (pintype "power_in"))
      (node (ref "IC14") (pin "1") (pinfunction "VCC_1") (pintype "power_in"))
      (node (ref "IC15") (pin "8") (pinfunction "VCC_8") (pintype "power_in"))
      (node (ref "IC21") (pin "8") (pinfunction "VCC_8") (pintype "power_in"))
      (node (ref "IC4") (pin "1") (pinfunction "VCC_1") (pintype "power_in"))
      (node (ref "IC6") (pin "8") (pinfunction "VCC_8") (pintype "power_in"))
    )
    (net (code "78") (name "P3V3_MP") (class "Default")
      (node (ref "C100") (pin "2") (pinfunction "2_2") (pintype "passive"))
      (node (ref "C65") (pin "2") (pinfunction "2_2") (pintype "passive"))
      (node (ref "C75") (pin "2") (pinfunction "2_2") (pintype "passive"))
      (node (ref "C76") (pin "2") (pinfunction "2_2") (pintype "passive"))
      (node (ref "D12") (pin "1") (pinfunction "C_1") (pintype "passive"))
      (node (ref "D6") (pin "4") (pinfunction "VCC_4") (pintype "power_in"))
      (node (ref "IC16") (pin "4") (pinfunction "VCC_4") (pintype "power_in"))
      (node (ref "IC26") (pin "8") (pinfunction "+VS_8") (pintype "power_in"))
      (node (ref "IC27") (pin "7") (pinfunction "A0_7") (pintype "input"))
      (node (ref "IC27") (pin "8") (pinfunction "+VS_8") (pintype "power_in"))
      (node (ref "IC32") (pin "14") (pinfunction "VCC_14") (pintype "power_in"))
      (node (ref "J9") (pin "30") (pinfunction "30_30") (pintype "bidirectional"))
      (node (ref "R61") (pin "1") (pinfunction "1_1") (pintype "passive"))
    )
    (net (code "79") (name "P12V0") (class "Default")
      (node (ref "C99") (pin "2") (pinfunction "2_2") (pintype "passive"))
      (node (ref "J9") (pin "28") (pinfunction "28_28") (pintype "bidirectional"))
      (node (ref "J9") (pin "29") (pinfunction "29_29") (pintype "bidirectional"))
      (node (ref "R51") (pin "2") (pinfunction "2_2") (pintype "passive"))
      (node (ref "T13") (pin "1") (pinfunction "S_1") (pintype "passive"))
      (node (ref "T13") (pin "2") (pinfunction "S_2") (pintype "passive"))
      (node (ref "T13") (pin "3") (pinfunction "S_3") (pintype "passive"))
    )
    (net (code "80") (name "P12V0_SW") (class "Default")
      (node (ref "T13") (pin "5") (pinfunction "D_5") (pintype "passive"))
      (node (ref "T13") (pin "6") (pinfunction "D_6") (pintype "passive"))
      (node (ref "T13") (pin "7") (pinfunction "D_7") (pintype "passive"))
      (node (ref "T13") (pin "8") (pinfunction "D_8") (pintype "passive"))
    )
    (net (code "81") (name "unconnected-(IC4-DIN2RIN--Pad3)") (class "Default")
      (node (ref "IC4") (pin "3") (pinfunction "DIN2RIN-_3") (pintype "input+no_connect"))
    )
    (net (code "82") (name "unconnected-(IC4-DOUT+-Pad6)") (class "Default")
      (node (ref "IC4") (pin "6") (pinfunction "DOUT+_6") (pintype "output+no_connect"))
    )
    (net (code "83") (name "unconnected-(IC4-DOUT--Pad5)") (class "Default")
      (node (ref "IC4") (pin "5") (pinfunction "DOUT-_5") (pintype "output+no_connect"))
    )
    (net (code "84") (name "unconnected-(IC13-RIN2+-Pad3)") (class "Default")
      (node (ref "IC13") (pin "3") (pinfunction "RIN2+_3") (pintype "input+no_connect"))
    )
    (net (code "85") (name "unconnected-(IC13-RIN2--Pad4)") (class "Default")
      (node (ref "IC13") (pin "4") (pinfunction "RIN2-_4") (pintype "input+no_connect"))
    )
    (net (code "86") (name "unconnected-(IC13-ROUT2-Pad6)") (class "Default")
      (node (ref "IC13") (pin "6") (pinfunction "ROUT2_6") (pintype "output+no_connect"))
    )
    (net (code "87") (name "unconnected-(IC16-NC-Pad5)") (class "Default")
      (node (ref "IC16") (pin "5") (pinfunction "NC_5") (pintype "passive"))
    )
  )
)
